# DCDCHalfBridgeFinished.net
KiCad netlist of a schematic drawn in EAGLE
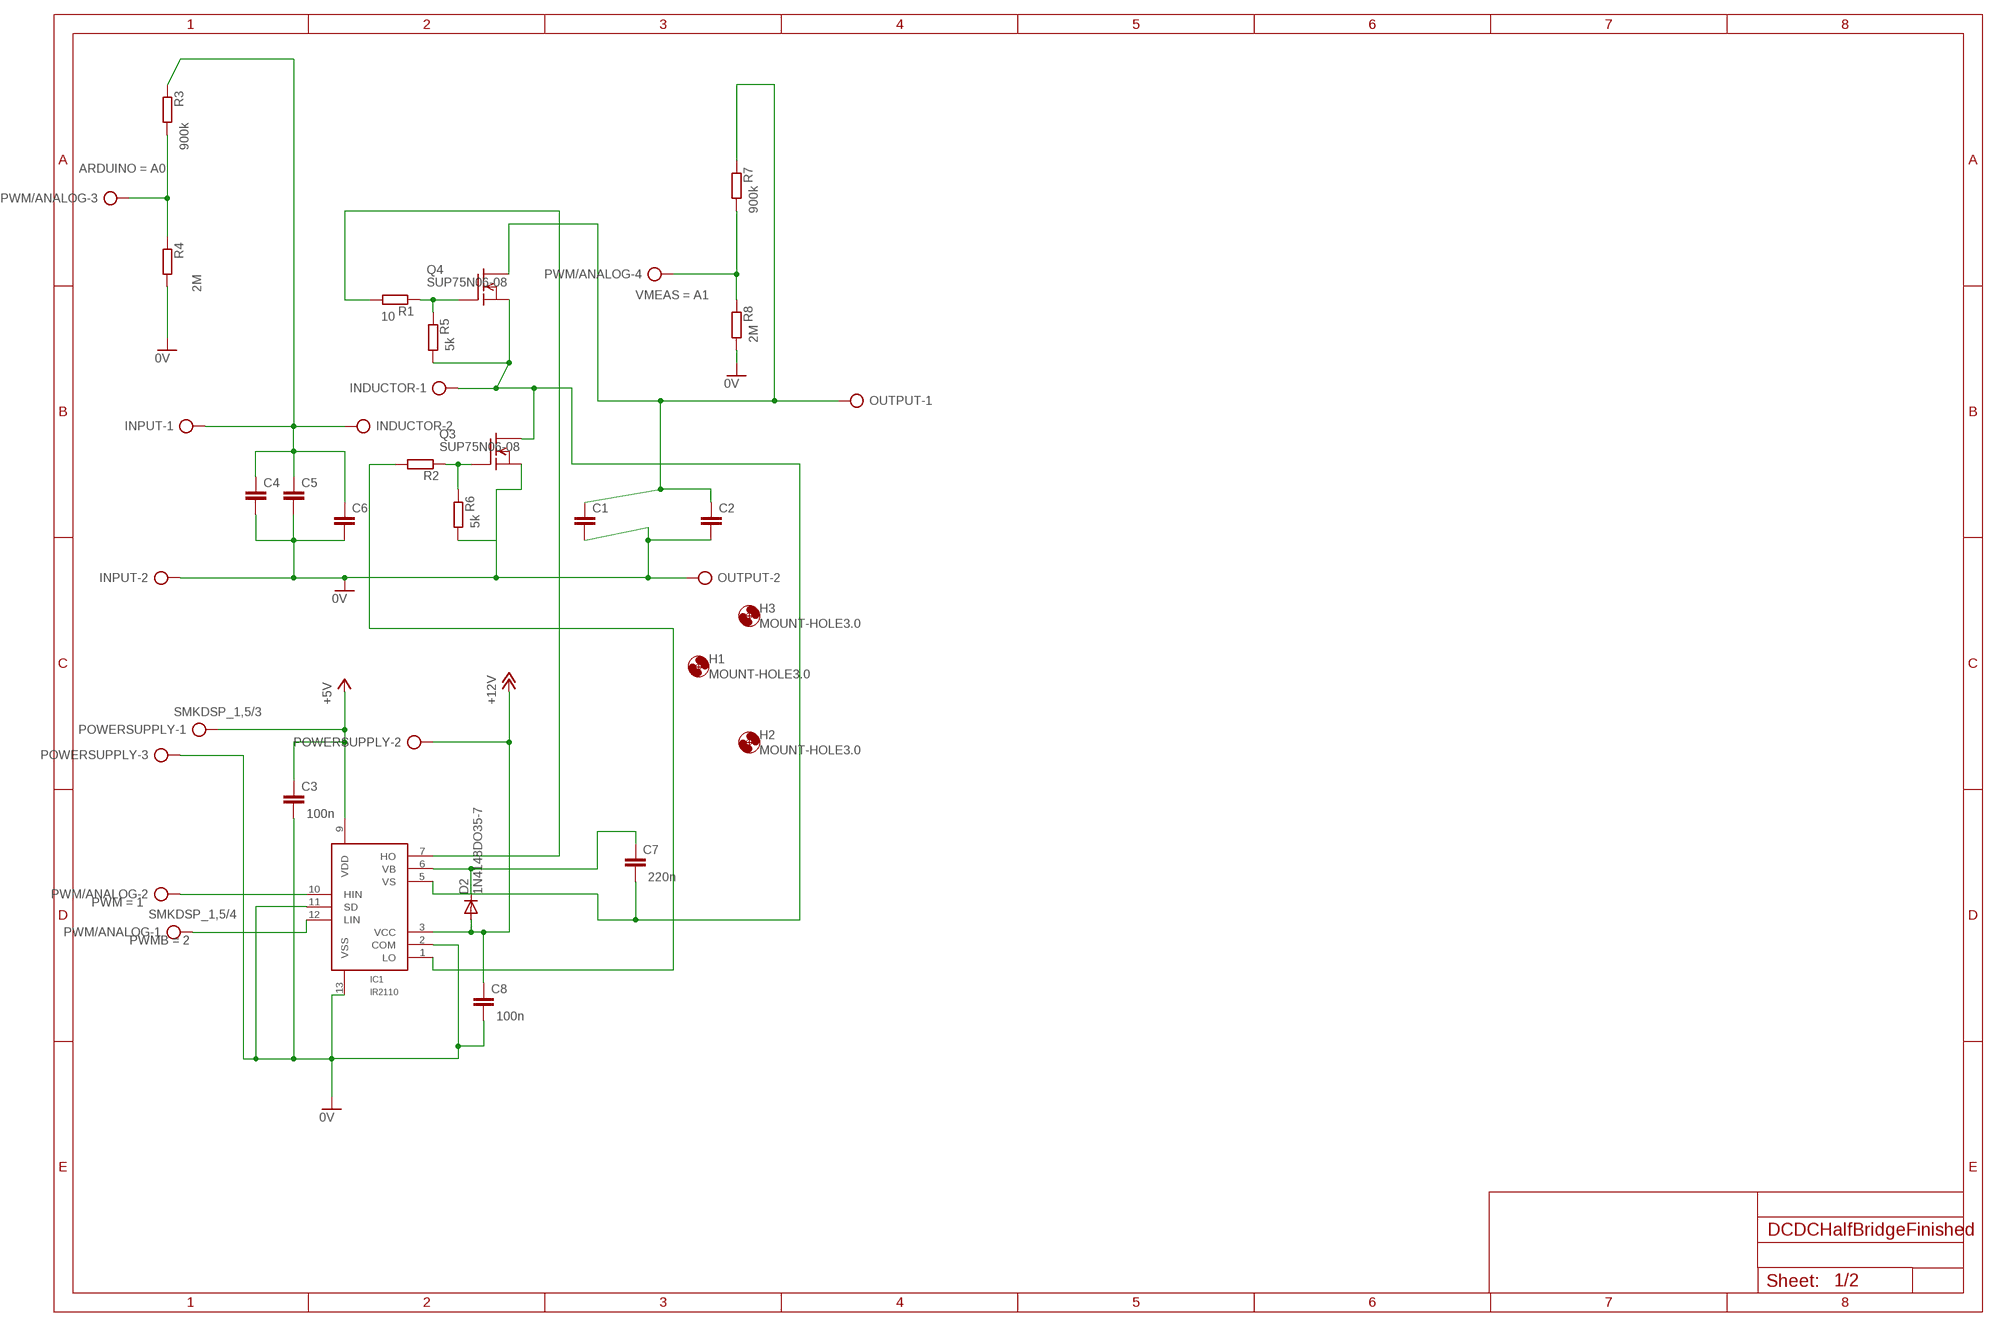
[diagram p0: schematic, sheet 1]
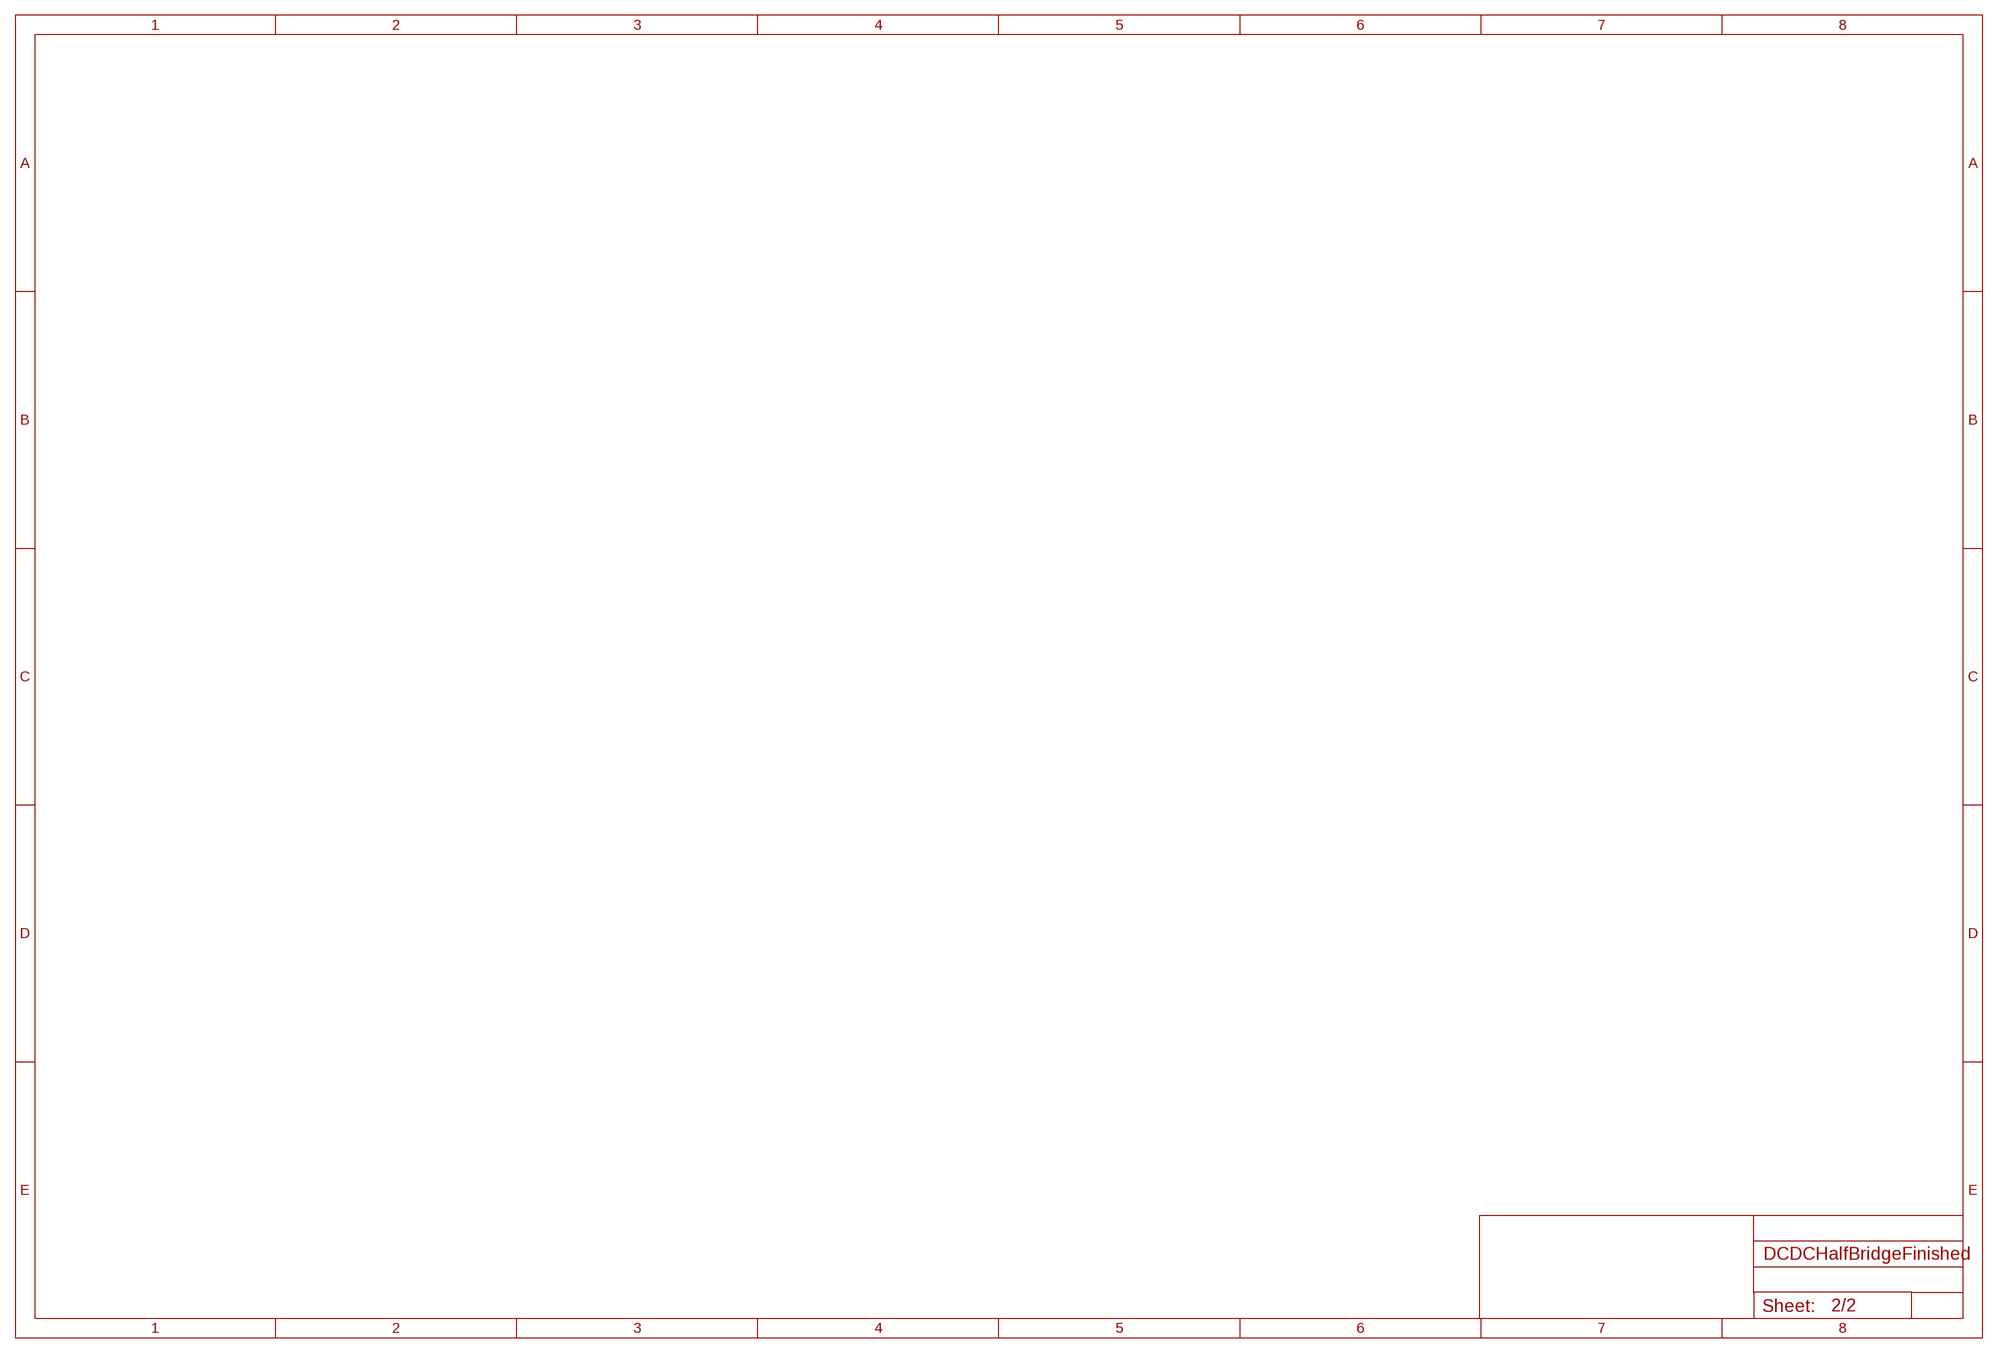
[diagram p1: schematic, sheet 2]

(export (version "E")
  (design (tool "Eeschema 10.0.6"))
  (components
    (comp (ref "C1")
      (value "C-EU050-025X075")
      (footprint "eagle-import:C050-025X075")
      (libsource (lib "eagle-import") (part "C-EU050-025X075"))
    )
    (comp (ref "C2")
      (value "C-EU050-025X075")
      (footprint "eagle-import:C050-025X075")
      (libsource (lib "eagle-import") (part "C-EU050-025X075"))
    )
    (comp (ref "C3")
      (value "C-EU025-025X050")
      (footprint "eagle-import:C025-025X050")
      (fields (field (name "C3") "100n"))
      (libsource (lib "eagle-import") (part "C-EU025-025X050"))
    )
    (comp (ref "C4")
      (value "C-EU050-025X075")
      (footprint "eagle-import:C050-025X075")
      (libsource (lib "eagle-import") (part "C-EU050-025X075"))
    )
    (comp (ref "C5")
      (value "C-EU050-025X075")
      (footprint "eagle-import:C050-025X075")
      (libsource (lib "eagle-import") (part "C-EU050-025X075"))
    )
    (comp (ref "C6")
      (value "C-EU050-025X075")
      (footprint "eagle-import:C050-025X075")
      (libsource (lib "eagle-import") (part "C-EU050-025X075"))
    )
    (comp (ref "C7")
      (value "C-EU025-025X050")
      (footprint "eagle-import:C025-025X050")
      (fields (field (name "C4") "220n"))
      (libsource (lib "eagle-import") (part "C-EU025-025X050"))
    )
    (comp (ref "C8")
      (value "C-EU025-025X050")
      (footprint "eagle-import:C025-025X050")
      (fields (field (name "C3") "100n"))
      (libsource (lib "eagle-import") (part "C-EU025-025X050"))
    )
    (comp (ref "D2")
      (value "1N4148DO35-7")
      (footprint "eagle-import:DO35-7")
      (libsource (lib "eagle-import") (part "1N4148DO35-7"))
    )
    (comp (ref "H1")
      (value "MOUNT-HOLE3.0")
      (footprint "eagle-import:3,0")
      (libsource (lib "eagle-import") (part "MOUNT-HOLE3.0"))
    )
    (comp (ref "H2")
      (value "MOUNT-HOLE3.0")
      (footprint "eagle-import:3,0")
      (libsource (lib "eagle-import") (part "MOUNT-HOLE3.0"))
    )
    (comp (ref "H3")
      (value "MOUNT-HOLE3.0")
      (footprint "eagle-import:3,0")
      (libsource (lib "eagle-import") (part "MOUNT-HOLE3.0"))
    )
    (comp (ref "IC1")
      (value "IR2110")
      (footprint "eagle-import:DIL14")
      (libsource (lib "eagle-import") (part "IR2110"))
    )
    (comp (ref "INDUCTOR")
      (value "AK300/2")
      (footprint "eagle-import:AK300_2")
      (libsource (lib "eagle-import") (part "AK300/2"))
    )
    (comp (ref "INPUT")
      (value "AK300/2")
      (footprint "eagle-import:AK300_2")
      (libsource (lib "eagle-import") (part "AK300/2"))
    )
    (comp (ref "OUTPUT")
      (value "AK300/2")
      (footprint "eagle-import:AK300_2")
      (libsource (lib "eagle-import") (part "AK300/2"))
    )
    (comp (ref "POWERSUPPLY")
      (value "SMKDSP_1,5/3")
      (footprint "eagle-import:SMKDSP_1,5_3")
      (fields (field (name "MF") "FARNELL") (field (name "MPN") "1733583"))
      (libsource (lib "eagle-import") (part "SMKDSP_1,5/3"))
    )
    (comp (ref "PWM/ANALOG")
      (value "SMKDSP_1,5/4")
      (footprint "eagle-import:SMKDSP_1,5_4")
      (fields
        (field (name "MF") "FARNELL")
        (field (name "MPN") "1733596")
        (field (name "ARDUINO") "A0")
        (field (name "PWM") "1")
        (field (name "PWMB") "2")
        (field (name "VMEAS") "A1")
      )
      (libsource (lib "eagle-import") (part "SMKDSP_1,5/4"))
    )
    (comp (ref "Q3")
      (value "SUP75N06-08")
      (footprint "eagle-import:TO220")
      (libsource (lib "eagle-import") (part "SUP75N06-08"))
    )
    (comp (ref "Q4")
      (value "SUP75N06-08")
      (footprint "eagle-import:TO220")
      (libsource (lib "eagle-import") (part "SUP75N06-08"))
    )
    (comp (ref "R1")
      (value "R-EU_0204/7")
      (footprint "eagle-import:0204_7")
      (fields (field (name "R1") "10"))
      (libsource (lib "eagle-import") (part "R-EU_0204/7"))
    )
    (comp (ref "R2")
      (value "R-EU_0204/7")
      (footprint "eagle-import:0204_7")
      (fields (field (name "R2") "10"))
      (libsource (lib "eagle-import") (part "R-EU_0204/7"))
    )
    (comp (ref "R3")
      (value "R-EU_0204/7")
      (footprint "eagle-import:0204_7")
      (fields (field (name "R1") "900k"))
      (libsource (lib "eagle-import") (part "R-EU_0204/7"))
    )
    (comp (ref "R4")
      (value "R-EU_0204/7")
      (footprint "eagle-import:0204_7")
      (fields (field (name "R1") "2M"))
      (libsource (lib "eagle-import") (part "R-EU_0204/7"))
    )
    (comp (ref "R5")
      (value "R-EU_0204/7")
      (footprint "eagle-import:0204_7")
      (fields (field (name "R1") "5k"))
      (libsource (lib "eagle-import") (part "R-EU_0204/7"))
    )
    (comp (ref "R6")
      (value "R-EU_0204/7")
      (footprint "eagle-import:0204_7")
      (fields (field (name "R1") "5k"))
      (libsource (lib "eagle-import") (part "R-EU_0204/7"))
    )
    (comp (ref "R7")
      (value "R-EU_0204/7")
      (footprint "eagle-import:0204_7")
      (fields (field (name "R1") "900k"))
      (libsource (lib "eagle-import") (part "R-EU_0204/7"))
    )
    (comp (ref "R8")
      (value "R-EU_0204/7")
      (footprint "eagle-import:0204_7")
      (fields (field (name "R1") "2M"))
      (libsource (lib "eagle-import") (part "R-EU_0204/7"))
    )
  )
  (nets
    (net (code "1") (name "+5V") (class "Default")
      (node (ref "C3") (pin "1") (pinfunction "1_1") (pintype "passive"))
      (node (ref "IC1") (pin "9") (pinfunction "VDD_9") (pintype "bidirectional"))
      (node (ref "POWERSUPPLY") (pin "1") (pinfunction "KL_1") (pintype "passive"))
    )
    (net (code "2") (name "+12V") (class "Default")
      (node (ref "C8") (pin "1") (pinfunction "1_1") (pintype "passive"))
      (node (ref "D2") (pin "A") (pinfunction "A_A") (pintype "passive"))
      (node (ref "IC1") (pin "3") (pinfunction "VCC_3") (pintype "bidirectional"))
      (node (ref "POWERSUPPLY") (pin "2") (pinfunction "KL_2") (pintype "passive"))
    )
    (net (code "3") (name "GND") (class "Default")
      (node (ref "C1") (pin "2") (pinfunction "2_2") (pintype "passive"))
      (node (ref "C2") (pin "2") (pinfunction "2_2") (pintype "passive"))
      (node (ref "C3") (pin "2") (pinfunction "2_2") (pintype "passive"))
      (node (ref "C4") (pin "2") (pinfunction "2_2") (pintype "passive"))
      (node (ref "C5") (pin "2") (pinfunction "2_2") (pintype "passive"))
      (node (ref "C6") (pin "2") (pinfunction "2_2") (pintype "passive"))
      (node (ref "C8") (pin "2") (pinfunction "2_2") (pintype "passive"))
      (node (ref "IC1") (pin "11") (pinfunction "SD_11") (pintype "bidirectional"))
      (node (ref "IC1") (pin "13") (pinfunction "VSS_13") (pintype "bidirectional"))
      (node (ref "IC1") (pin "2") (pinfunction "COM_2") (pintype "bidirectional"))
      (node (ref "INPUT") (pin "2") (pinfunction "KL_2") (pintype "passive"))
      (node (ref "OUTPUT") (pin "2") (pinfunction "KL_2") (pintype "passive"))
      (node (ref "POWERSUPPLY") (pin "3") (pinfunction "KL_3") (pintype "passive"))
      (node (ref "Q3") (pin "3") (pinfunction "S_3") (pintype "passive"))
      (node (ref "R4") (pin "2") (pinfunction "2_2") (pintype "passive"))
      (node (ref "R6") (pin "2") (pinfunction "2_2") (pintype "passive"))
      (node (ref "R8") (pin "2") (pinfunction "2_2") (pintype "passive"))
    )
    (net (code "4") (name "Net-(IC1-HIN)") (class "Default")
      (node (ref "IC1") (pin "10") (pinfunction "HIN_10") (pintype "bidirectional"))
      (node (ref "PWM/ANALOG") (pin "2") (pinfunction "KL_2") (pintype "passive"))
    )
    (net (code "5") (name "Net-(IC1-HO)") (class "Default")
      (node (ref "IC1") (pin "7") (pinfunction "HO_7") (pintype "bidirectional"))
      (node (ref "R1") (pin "2") (pinfunction "2_2") (pintype "passive"))
    )
    (net (code "6") (name "Net-(IC1-LIN)") (class "Default")
      (node (ref "IC1") (pin "12") (pinfunction "LIN_12") (pintype "bidirectional"))
      (node (ref "PWM/ANALOG") (pin "1") (pinfunction "KL_1") (pintype "passive"))
    )
    (net (code "7") (name "Net-(IC1-LO)") (class "Default")
      (node (ref "IC1") (pin "1") (pinfunction "LO_1") (pintype "bidirectional"))
      (node (ref "R2") (pin "2") (pinfunction "2_2") (pintype "passive"))
    )
    (net (code "8") (name "Net-(IC1-VB)") (class "Default")
      (node (ref "C7") (pin "1") (pinfunction "1_1") (pintype "passive"))
      (node (ref "D2") (pin "C") (pinfunction "C_C") (pintype "passive"))
      (node (ref "IC1") (pin "6") (pinfunction "VB_6") (pintype "bidirectional"))
    )
    (net (code "9") (name "Net-(IC1-VS)") (class "Default")
      (node (ref "C7") (pin "2") (pinfunction "2_2") (pintype "passive"))
      (node (ref "IC1") (pin "5") (pinfunction "VS_5") (pintype "bidirectional"))
      (node (ref "INDUCTOR") (pin "1") (pinfunction "KL_1") (pintype "passive"))
      (node (ref "Q3") (pin "2") (pinfunction "D_2") (pintype "passive"))
      (node (ref "Q4") (pin "3") (pinfunction "S_3") (pintype "passive"))
      (node (ref "R5") (pin "2") (pinfunction "2_2") (pintype "passive"))
    )
    (net (code "10") (name "Net-(INDUCTORB-KL)") (class "Default")
      (node (ref "C4") (pin "1") (pinfunction "1_1") (pintype "passive"))
      (node (ref "C5") (pin "1") (pinfunction "1_1") (pintype "passive"))
      (node (ref "C6") (pin "1") (pinfunction "1_1") (pintype "passive"))
      (node (ref "INDUCTOR") (pin "2") (pinfunction "KL_2") (pintype "passive"))
      (node (ref "INPUT") (pin "1") (pinfunction "KL_1") (pintype "passive"))
      (node (ref "R3") (pin "1") (pinfunction "1_1") (pintype "passive"))
    )
    (net (code "11") (name "Net-(OUTPUTA-KL)") (class "Default")
      (node (ref "C1") (pin "1") (pinfunction "1_1") (pintype "passive"))
      (node (ref "C2") (pin "1") (pinfunction "1_1") (pintype "passive"))
      (node (ref "OUTPUT") (pin "1") (pinfunction "KL_1") (pintype "passive"))
      (node (ref "Q4") (pin "2") (pinfunction "D_2") (pintype "passive"))
      (node (ref "R7") (pin "1") (pinfunction "1_1") (pintype "passive"))
    )
    (net (code "12") (name "Net-(PWM/ANALOGC-KL)") (class "Default")
      (node (ref "PWM/ANALOG") (pin "3") (pinfunction "KL_3") (pintype "passive"))
      (node (ref "R3") (pin "2") (pinfunction "2_2") (pintype "passive"))
      (node (ref "R4") (pin "1") (pinfunction "1_1") (pintype "passive"))
    )
    (net (code "13") (name "Net-(PWM/ANALOGD-KL)") (class "Default")
      (node (ref "PWM/ANALOG") (pin "4") (pinfunction "KL_4") (pintype "passive"))
      (node (ref "R7") (pin "2") (pinfunction "2_2") (pintype "passive"))
      (node (ref "R8") (pin "1") (pinfunction "1_1") (pintype "passive"))
    )
    (net (code "14") (name "Net-(Q3-G)") (class "Default")
      (node (ref "Q3") (pin "1") (pinfunction "G_1") (pintype "passive"))
      (node (ref "R2") (pin "1") (pinfunction "1_1") (pintype "passive"))
      (node (ref "R6") (pin "1") (pinfunction "1_1") (pintype "passive"))
    )
    (net (code "15") (name "Net-(Q4-G)") (class "Default")
      (node (ref "Q4") (pin "1") (pinfunction "G_1") (pintype "passive"))
      (node (ref "R1") (pin "1") (pinfunction "1_1") (pintype "passive"))
      (node (ref "R5") (pin "1") (pinfunction "1_1") (pintype "passive"))
    )
  )
)
